# RS485.net
KiCad netlist of a schematic drawn in EAGLE
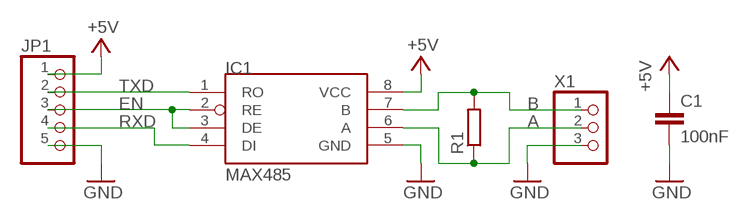
[diagram p0: schematic, sheet 1]

(export (version "E")
  (design (tool "Eeschema 10.0.6"))
  (components
    (comp (ref "C1")
      (value "100nF")
      (footprint "eagle-import:C0805K")
      (libsource (lib "eagle-import") (part "C-EUC0805K"))
    )
    (comp (ref "IC1")
      (value "MAX485")
      (footprint "eagle-import:SO08")
      (libsource (lib "eagle-import") (part "MAX485"))
    )
    (comp (ref "JP1")
      (value "PINHD-1X5")
      (footprint "eagle-import:1X05")
      (libsource (lib "eagle-import") (part "PINHD-1X5"))
    )
    (comp (ref "R1")
      (value "R-EU_R0805")
      (footprint "eagle-import:R0805")
      (libsource (lib "eagle-import") (part "R-EU_R0805"))
    )
    (comp (ref "X1")
      (value "W237-103")
      (footprint "eagle-import:W237-103")
      (libsource (lib "eagle-import") (part "W237-103"))
    )
  )
  (nets
    (net (code "1") (name "+5V") (class "Default")
      (node (ref "C1") (pin "1") (pinfunction "1_1") (pintype "passive"))
      (node (ref "IC1") (pin "8") (pinfunction "VCC_8") (pintype "bidirectional"))
      (node (ref "JP1") (pin "1") (pinfunction "1_1") (pintype "passive"))
    )
    (net (code "2") (name "/A") (class "Default")
      (node (ref "IC1") (pin "6") (pinfunction "A_6") (pintype "bidirectional"))
      (node (ref "R1") (pin "1") (pinfunction "1_1") (pintype "passive"))
      (node (ref "X1") (pin "2") (pinfunction "2_2") (pintype "passive"))
    )
    (net (code "3") (name "/B") (class "Default")
      (node (ref "IC1") (pin "7") (pinfunction "B_7") (pintype "bidirectional"))
      (node (ref "R1") (pin "2") (pinfunction "2_2") (pintype "passive"))
      (node (ref "X1") (pin "1") (pinfunction "1_1") (pintype "passive"))
    )
    (net (code "4") (name "/EN") (class "Default")
      (node (ref "IC1") (pin "2") (pinfunction "RE_2") (pintype "bidirectional"))
      (node (ref "IC1") (pin "3") (pinfunction "DE_3") (pintype "bidirectional"))
      (node (ref "JP1") (pin "3") (pinfunction "3_3") (pintype "passive"))
    )
    (net (code "5") (name "/RXD") (class "Default")
      (node (ref "IC1") (pin "4") (pinfunction "DI_4") (pintype "bidirectional"))
      (node (ref "JP1") (pin "4") (pinfunction "4_4") (pintype "passive"))
    )
    (net (code "6") (name "/TXD") (class "Default")
      (node (ref "IC1") (pin "1") (pinfunction "RO_1") (pintype "bidirectional"))
      (node (ref "JP1") (pin "2") (pinfunction "2_2") (pintype "passive"))
    )
    (net (code "7") (name "GND") (class "Default")
      (node (ref "C1") (pin "2") (pinfunction "2_2") (pintype "passive"))
      (node (ref "IC1") (pin "5") (pinfunction "GND_5") (pintype "bidirectional"))
      (node (ref "JP1") (pin "5") (pinfunction "5_5") (pintype "passive"))
      (node (ref "X1") (pin "3") (pinfunction "3_3") (pintype "passive"))
    )
  )
)
